# waterDropCapture.net
KiCad netlist of a schematic drawn in EAGLE
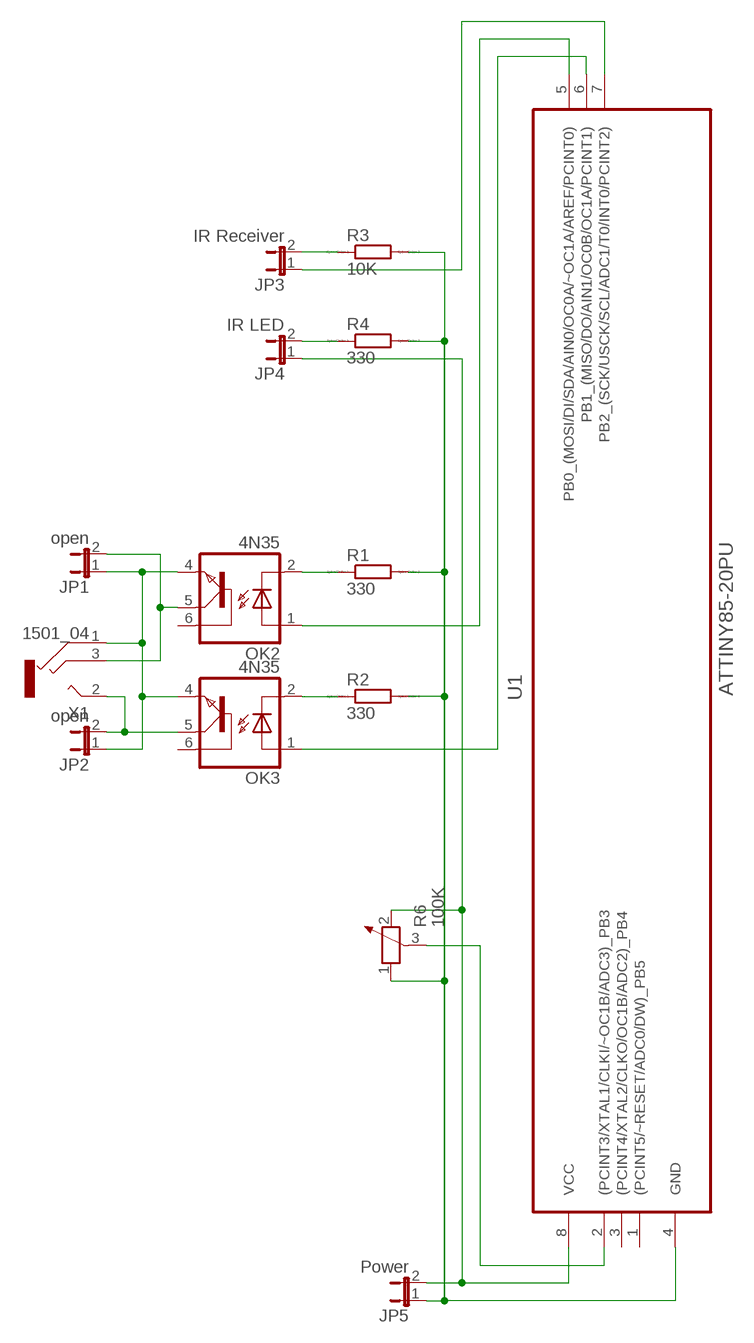
[diagram p0: schematic, sheet 1]

(export (version "E")
  (design (tool "Eeschema 10.0.6"))
  (components
    (comp (ref "JP1")
      (value "open")
      (footprint "eagle-import:JP1")
      (libsource (lib "eagle-import") (part "JP1E"))
    )
    (comp (ref "JP2")
      (value "open")
      (footprint "eagle-import:JP1")
      (libsource (lib "eagle-import") (part "JP1E"))
    )
    (comp (ref "JP3")
      (value "IR Receiver")
      (footprint "eagle-import:JP1")
      (libsource (lib "eagle-import") (part "JP1E"))
    )
    (comp (ref "JP4")
      (value "IR LED")
      (footprint "eagle-import:JP1")
      (libsource (lib "eagle-import") (part "JP1E"))
    )
    (comp (ref "JP5")
      (value "Power")
      (footprint "eagle-import:JP1")
      (libsource (lib "eagle-import") (part "JP1E"))
    )
    (comp (ref "OK2")
      (value "4N35")
      (footprint "eagle-import:DIL06")
      (fields (field (name "MF") "FAIRCHILD SEMICONDUCTOR"))
      (libsource (lib "eagle-import") (part "4N35"))
    )
    (comp (ref "OK3")
      (value "4N35")
      (footprint "eagle-import:DIL06")
      (fields (field (name "MF") "FAIRCHILD SEMICONDUCTOR"))
      (libsource (lib "eagle-import") (part "4N35"))
    )
    (comp (ref "R1")
      (value "330")
      (footprint "eagle-import:0207_10")
      (libsource (lib "eagle-import") (part "R0207/10"))
    )
    (comp (ref "R2")
      (value "330")
      (footprint "eagle-import:0207_10")
      (libsource (lib "eagle-import") (part "R0207/10"))
    )
    (comp (ref "R3")
      (value "10K")
      (footprint "eagle-import:0207_10")
      (libsource (lib "eagle-import") (part "R0207/10"))
    )
    (comp (ref "R4")
      (value "330")
      (footprint "eagle-import:0207_10")
      (libsource (lib "eagle-import") (part "R0207/10"))
    )
    (comp (ref "R6")
      (value "100K")
      (footprint "eagle-import:PT-10")
      (libsource (lib "eagle-import") (part "POTENTIOMETER_PT-10"))
    )
    (comp (ref "U1")
      (value "ATTINY85-20PU")
      (footprint "eagle-import:DIP254P762X533-8")
      (libsource (lib "eagle-import") (part "ATTINY85-20PU"))
    )
    (comp (ref "X1")
      (value "1501_04")
      (footprint "eagle-import:1501_05")
      (libsource (lib "eagle-import") (part "1501_04"))
    )
  )
  (nets
    (net (code "1") (name "Net-(JP3-Pad2)") (class "Default")
      (node (ref "JP3") (pin "2") (pinfunction "2_2") (pintype "passive"))
      (node (ref "R3") (pin "1") (pinfunction "1_1") (pintype "passive"))
    )
    (net (code "2") (name "Net-(JP4-Pad2)") (class "Default")
      (node (ref "JP4") (pin "2") (pinfunction "2_2") (pintype "passive"))
      (node (ref "R4") (pin "1") (pinfunction "1_1") (pintype "passive"))
    )
    (net (code "3") (name "Net-(OK2-A)") (class "Default")
      (node (ref "OK2") (pin "1") (pinfunction "A_1") (pintype "passive"))
      (node (ref "U1") (pin "5") (pinfunction "PB0_(MOSI/DI/SDA/AIN0/OC0A/~{OC1A/AREF/PCINT0})_5") (pintype "bidirectional"))
    )
    (net (code "4") (name "Net-(OK2-C)") (class "Default")
      (node (ref "OK2") (pin "2") (pinfunction "C_2") (pintype "passive"))
      (node (ref "R1") (pin "1") (pinfunction "1_1") (pintype "passive"))
    )
    (net (code "5") (name "Net-(OK2-COL)") (class "Default")
      (node (ref "JP1") (pin "2") (pinfunction "2_2") (pintype "passive"))
      (node (ref "OK2") (pin "5") (pinfunction "COL_5") (pintype "passive"))
      (node (ref "X1") (pin "3") (pinfunction "3_3") (pintype "passive"))
    )
    (net (code "6") (name "Net-(OK2-EMI)") (class "Default")
      (node (ref "JP1") (pin "1") (pinfunction "1_1") (pintype "passive"))
      (node (ref "JP2") (pin "1") (pinfunction "1_1") (pintype "passive"))
      (node (ref "OK2") (pin "4") (pinfunction "EMI_4") (pintype "passive"))
      (node (ref "OK3") (pin "4") (pinfunction "EMI_4") (pintype "passive"))
      (node (ref "X1") (pin "1") (pinfunction "1_1") (pintype "passive"))
    )
    (net (code "7") (name "Net-(OK3-A)") (class "Default")
      (node (ref "OK3") (pin "1") (pinfunction "A_1") (pintype "passive"))
      (node (ref "U1") (pin "6") (pinfunction "PB1_(MISO/DO/AIN1/OC0B/OC1A/PCINT1)_6") (pintype "bidirectional"))
    )
    (net (code "8") (name "Net-(OK3-C)") (class "Default")
      (node (ref "OK3") (pin "2") (pinfunction "C_2") (pintype "passive"))
      (node (ref "R2") (pin "1") (pinfunction "1_1") (pintype "passive"))
    )
    (net (code "9") (name "Net-(OK3-COL)") (class "Default")
      (node (ref "JP2") (pin "2") (pinfunction "2_2") (pintype "passive"))
      (node (ref "OK3") (pin "5") (pinfunction "COL_5") (pintype "passive"))
      (node (ref "X1") (pin "2") (pinfunction "2_2") (pintype "passive"))
    )
    (net (code "10") (name "Net-(U1-(PCINT3{slash}XTAL1{slash}CLKI{slash}~{OC1B{slash}ADC3})_PB3)") (class "Default")
      (node (ref "R6") (pin "3") (pinfunction "3_3") (pintype "passive"))
      (node (ref "U1") (pin "2") (pinfunction "(PCINT3/XTAL1/CLKI/~{OC1B/ADC3})_PB3_2") (pintype "bidirectional"))
    )
    (net (code "11") (name "Net-(U1-GND)") (class "Default")
      (node (ref "JP5") (pin "1") (pinfunction "1_1") (pintype "passive"))
      (node (ref "R1") (pin "2") (pinfunction "2_2") (pintype "passive"))
      (node (ref "R2") (pin "2") (pinfunction "2_2") (pintype "passive"))
      (node (ref "R3") (pin "2") (pinfunction "2_2") (pintype "passive"))
      (node (ref "R4") (pin "2") (pinfunction "2_2") (pintype "passive"))
      (node (ref "R6") (pin "1") (pinfunction "1_1") (pintype "passive"))
      (node (ref "U1") (pin "4") (pinfunction "GND_4") (pintype "passive"))
    )
    (net (code "12") (name "Net-(U1-PB2_(SCK{slash}USCK{slash}SCL{slash}ADC1{slash}T0{slash}INT0{slash}PCINT2))") (class "Default")
      (node (ref "JP3") (pin "1") (pinfunction "1_1") (pintype "passive"))
      (node (ref "U1") (pin "7") (pinfunction "PB2_(SCK/USCK/SCL/ADC1/T0/INT0/PCINT2)_7") (pintype "bidirectional"))
    )
    (net (code "13") (name "Net-(U1-VCC)") (class "Default")
      (node (ref "JP4") (pin "1") (pinfunction "1_1") (pintype "passive"))
      (node (ref "JP5") (pin "2") (pinfunction "2_2") (pintype "passive"))
      (node (ref "R6") (pin "2") (pinfunction "2_2") (pintype "passive"))
      (node (ref "U1") (pin "8") (pinfunction "VCC_8") (pintype "power_in"))
    )
    (net (code "14") (name "unconnected-(OK2-BAS-Pad6)") (class "Default")
      (node (ref "OK2") (pin "6") (pinfunction "BAS_6") (pintype "passive"))
    )
    (net (code "15") (name "unconnected-(OK3-BAS-Pad6)") (class "Default")
      (node (ref "OK3") (pin "6") (pinfunction "BAS_6") (pintype "passive"))
    )
    (net (code "16") (name "unconnected-(U1-(PCINT4{slash}XTAL2{slash}CLKO{slash}OC1B{slash}ADC2)_PB4-Pad3)") (class "Default")
      (node (ref "U1") (pin "3") (pinfunction "(PCINT4/XTAL2/CLKO/OC1B/ADC2)_PB4_3") (pintype "bidirectional"))
    )
    (net (code "17") (name "unconnected-(U1-(PCINT5{slash}~{RESET{slash}ADC0{slash}DW})_PB5-Pad1)") (class "Default")
      (node (ref "U1") (pin "1") (pinfunction "(PCINT5/~{RESET/ADC0/DW})_PB5_1") (pintype "bidirectional"))
    )
  )
)
